# BMS.net
KiCad netlist of a schematic drawn in Altium Designer
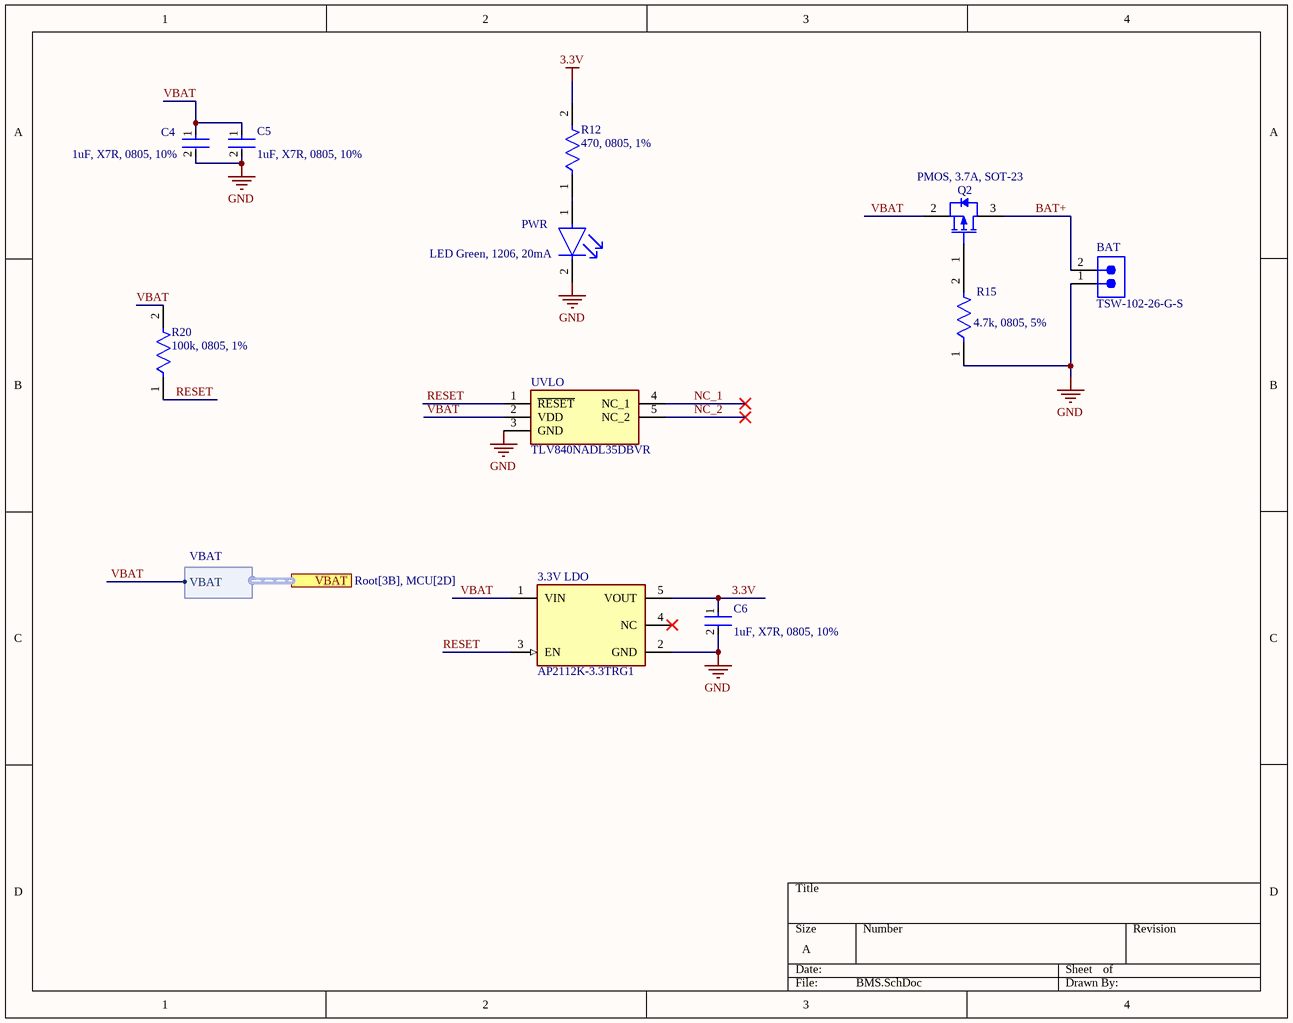
[diagram p0: BMS.SchDoc]

(export (version "E")
  (design (tool "Eeschema 10.0.6"))
  (components
    (comp (ref "3.3V LDO")
      (value "AP2112K-3.3TRG1")
      (footprint "FP-SOT25-IPC_A")
      (description "IC REG LINEAR 3.3V 600MA SOT25")
      (libsource (lib "Altium Content Vault") (part "c8ab751aee5229183125ab046a11caa"))
    )
    (comp (ref "BAT")
      (value "TSW-102-26-G-S")
      (footprint "SMTC-TSW-102-26-XX-S")
      (description "0.025\" SQ Post Header, Through-hole, Vertical, -55 to 125 degC, 2.54 mm Pitch, 2-Pin, Male, RoHS")
      (fields (field (name "MANUFACTURER") "Samtec"))
      (libsource (lib "Altium Content Vault") (part "SMTC-TSW-102-X-X-S-X"))
    )
    (comp (ref "C4")
      (value "1uF, X7R, 0805, 10%")
      (footprint "FP-CC0805-0_85-MFG")
      (description "CC0805 1 uF X7R 10.00% 50 V")
      (fields
        (field (name "MANUFACTURER PART NUMBER") "CC0805KFX7R9BB105")
        (field (name "OCTOPART") "https://octopart.com/cc0805kfx7r9bb105-yageo-76378930")
      )
      (libsource (lib "Altium Content Vault") (part "11868f565c42a9108669ba33697ecf6"))
    )
    (comp (ref "C5")
      (value "1uF, X7R, 0805, 10%")
      (footprint "FP-CC0805-0_85-MFG")
      (description "CC0805 1 uF X7R 10.00% 50 V")
      (fields
        (field (name "MANUFACTURER PART NUMBER") "CC0805KFX7R9BB105")
        (field (name "OCTOPART") "https://octopart.com/cc0805kfx7r9bb105-yageo-76378930")
      )
      (libsource (lib "Altium Content Vault") (part "11868f565c42a9108669ba33697ecf6"))
    )
    (comp (ref "C6")
      (value "1uF, X7R, 0805, 10%")
      (footprint "FP-CC0805-0_85-MFG")
      (description "CC0805 1 uF X7R 10.00% 50 V")
      (fields
        (field (name "MANUFACTURER PART NUMBER") "CC0805KFX7R9BB105")
        (field (name "OCTOPART") "https://octopart.com/cc0805kfx7r9bb105-yageo-76378930")
      )
      (libsource (lib "Altium Content Vault") (part "11868f565c42a9108669ba33697ecf6"))
    )
    (comp (ref "PWR")
      (value "LED Green, 1206, 20mA")
      (footprint "FP-SML-LX1206GC-TR-MFG")
      (description "LED GREEN CLEAR 1206 SMD")
      (libsource (lib "Altium Content Vault") (part "ab1c01a81903e929fc6c44469aada92"))
    )
    (comp (ref "Q2")
      (value "PMOS, 3.7A, SOT-23")
      (footprint "ONSC-SOT-23-3-318-08_V")
      (description "Small Signal MOSFET, -8 V, -3.7 A, Single P-Channel, 3-Pin SOT-23, Pb-Free, Tape and Reel")
      (fields (field (name "MANUFACTURER") "On Semiconductor") (field (name "PARTNUMBER") "NTR2101PT1G"))
      (libsource (lib "Altium Content Vault") (part "ONSC-PMOS-G1S2D3-3_D"))
    )
    (comp (ref "R12")
      (value "470, 0805, 1%")
      (footprint "FP-RMCF0805-IPC_C")
      (description "470Ω ±1% 0.125W 0805 Thick Film Chip Resistor AEC-Q200 compliant")
      (fields (field (name "TOLERANCE") "1%"))
      (libsource (lib "Altium Content Vault") (part "1029c3af85768c4190bb7ad29bc67b5"))
    )
    (comp (ref "R15")
      (value "4.7k, 0805, 5%")
      (footprint "FP-RMCF0805-MFG")
      (description "4.7kΩ ±5% 0.125W 0805 Thick Film Chip Resistor AEC-Q200 compliant")
      (fields (field (name "TOLERANCE") "5%"))
      (libsource (lib "Altium Content Vault") (part "1029c3af85768c4190bb7ad29bc67b5"))
    )
    (comp (ref "R20")
      (value "100k, 0805, 1%")
      (footprint "FP-CRGCQ0805-IPC_C")
      (description "CRGCQ 0805 100K 1%")
      (fields
        (field (name "MANUFACTURER") "TE Connectivity")
        (field (name "OCTOPART") "https://octopart.com/crgcq0805f100k-te+connectivity-91018138")
      )
      (libsource (lib "Altium Content Vault") (part "1029c3af85768c4190bb7ad29bc67b5"))
    )
    (comp (ref "UVLO")
      (value "TLV840NADL35DBVR")
      (footprint "SamacSys:SOT95P280X145-5N")
      (description "Integrated Circuit")
      (fields (field (name "MOUSER PART NUMBER") "595-TLV840NADL35DBVR"))
      (libsource (lib "*") (part "TLV840NADL35DBVR"))
    )
  )
  (nets
    (net (code "1") (name "/BAT+") (class "Default")
      (node (ref "BAT") (pin "2") (pinfunction "2_2") (pintype "passive"))
      (node (ref "Q2") (pin "3") (pinfunction "D_3") (pintype "passive"))
    )
    (net (code "2") (name "/NC_1") (class "Default")
      (node (ref "UVLO") (pin "4") (pinfunction "NC_1_4") (pintype "passive+no_connect"))
    )
    (net (code "3") (name "/NC_2") (class "Default")
      (node (ref "UVLO") (pin "5") (pinfunction "NC_2_5") (pintype "passive+no_connect"))
    )
    (net (code "4") (name "/RESET") (class "Default")
      (node (ref "3.3V LDO") (pin "3") (pinfunction "EN_3") (pintype "input"))
      (node (ref "R20") (pin "1") (pinfunction "1_1") (pintype "passive"))
      (node (ref "UVLO") (pin "1") (pinfunction "~{RESET}_1") (pintype "passive"))
    )
    (net (code "5") (name "/VBAT") (class "Default")
      (node (ref "3.3V LDO") (pin "1") (pinfunction "VIN_1") (pintype "power_in"))
      (node (ref "C4") (pin "1") (pinfunction "1_1") (pintype "passive"))
      (node (ref "C5") (pin "1") (pinfunction "1_1") (pintype "passive"))
      (node (ref "Q2") (pin "2") (pinfunction "S_2") (pintype "passive"))
      (node (ref "R20") (pin "2") (pinfunction "2_2") (pintype "passive"))
      (node (ref "UVLO") (pin "2") (pinfunction "VDD_2") (pintype "passive"))
    )
    (net (code "7") (name "3.3V") (class "Default")
      (node (ref "3.3V LDO") (pin "5") (pinfunction "VOUT_5") (pintype "power_in"))
      (node (ref "C6") (pin "1") (pinfunction "1_1") (pintype "passive"))
      (node (ref "R12") (pin "2") (pinfunction "2_2") (pintype "passive"))
    )
    (net (code "8") (name "GND") (class "Default")
      (node (ref "3.3V LDO") (pin "2") (pinfunction "GND_2") (pintype "power_in"))
      (node (ref "BAT") (pin "1") (pinfunction "1_1") (pintype "passive"))
      (node (ref "C4") (pin "2") (pinfunction "2_2") (pintype "passive"))
      (node (ref "C5") (pin "2") (pinfunction "2_2") (pintype "passive"))
      (node (ref "C6") (pin "2") (pinfunction "2_2") (pintype "passive"))
      (node (ref "PWR") (pin "2") (pinfunction "C_2") (pintype "passive"))
      (node (ref "R15") (pin "1") (pinfunction "1_1") (pintype "passive"))
      (node (ref "UVLO") (pin "3") (pinfunction "GND_3") (pintype "passive"))
    )
    (net (code "9") (name "Net-(PWR-A)") (class "Default")
      (node (ref "PWR") (pin "1") (pinfunction "A_1") (pintype "passive"))
      (node (ref "R12") (pin "1") (pinfunction "1_1") (pintype "passive"))
    )
    (net (code "10") (name "Net-(Q2-G)") (class "Default")
      (node (ref "Q2") (pin "1") (pinfunction "G_1") (pintype "passive"))
      (node (ref "R15") (pin "2") (pinfunction "2_2") (pintype "passive"))
    )
    (net (code "11") (name "unconnected-(3.3V LDO-NC-Pad4)") (class "Default")
      (node (ref "3.3V LDO") (pin "4") (pinfunction "NC_4") (pintype "passive+no_connect"))
    )
  )
)
